# espDash.net
KiCad netlist of a schematic drawn in EAGLE
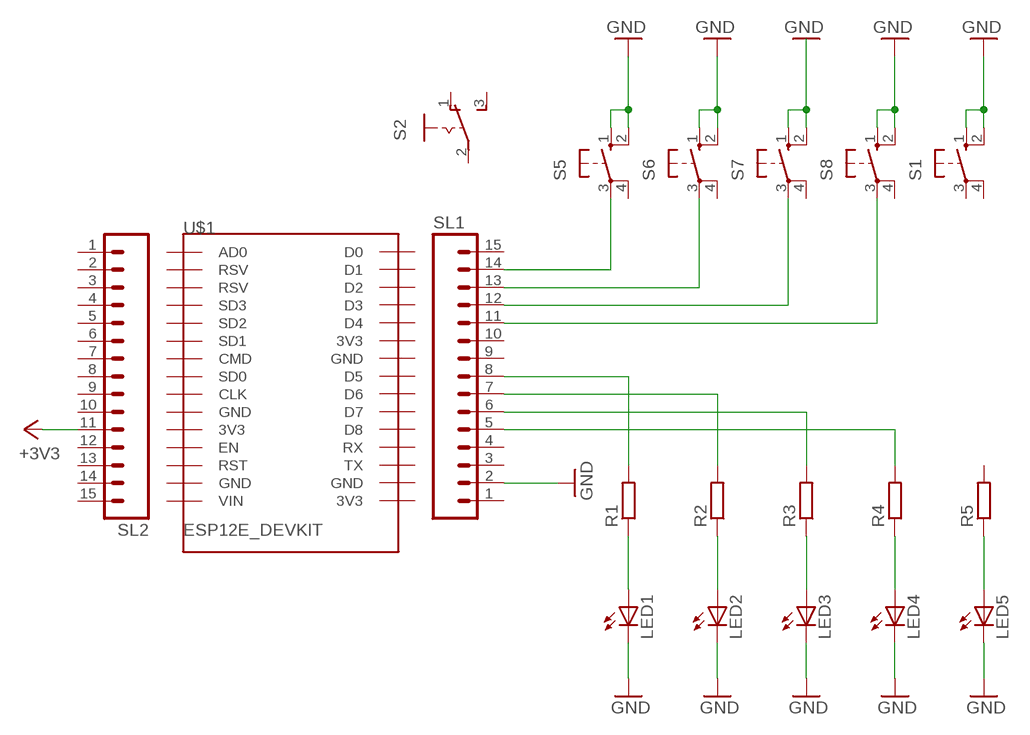
[diagram p0: schematic, sheet 1]

(export (version "E")
  (design (tool "Eeschema 10.0.6"))
  (components
    (comp (ref "LED1")
      (value "LED5MM")
      (footprint "eagle-import:LED5MM")
      (libsource (lib "eagle-import") (part "LED5MM"))
    )
    (comp (ref "LED2")
      (value "LED5MM")
      (footprint "eagle-import:LED5MM")
      (libsource (lib "eagle-import") (part "LED5MM"))
    )
    (comp (ref "LED3")
      (value "LED5MM")
      (footprint "eagle-import:LED5MM")
      (libsource (lib "eagle-import") (part "LED5MM"))
    )
    (comp (ref "LED4")
      (value "LED5MM")
      (footprint "eagle-import:LED5MM")
      (libsource (lib "eagle-import") (part "LED5MM"))
    )
    (comp (ref "LED5")
      (value "LED5MM")
      (footprint "eagle-import:LED5MM")
      (libsource (lib "eagle-import") (part "LED5MM"))
    )
    (comp (ref "R1")
      (value "R-EU_0207/10")
      (footprint "eagle-import:0207_10")
      (libsource (lib "eagle-import") (part "R-EU_0207/10"))
    )
    (comp (ref "R2")
      (value "R-EU_0207/10")
      (footprint "eagle-import:0207_10")
      (libsource (lib "eagle-import") (part "R-EU_0207/10"))
    )
    (comp (ref "R3")
      (value "R-EU_0207/10")
      (footprint "eagle-import:0207_10")
      (libsource (lib "eagle-import") (part "R-EU_0207/10"))
    )
    (comp (ref "R4")
      (value "R-EU_0207/10")
      (footprint "eagle-import:0207_10")
      (libsource (lib "eagle-import") (part "R-EU_0207/10"))
    )
    (comp (ref "R5")
      (value "R-EU_0207/10")
      (footprint "eagle-import:0207_10")
      (libsource (lib "eagle-import") (part "R-EU_0207/10"))
    )
    (comp (ref "S1")
      (value "40-XX")
      (footprint "eagle-import:B3F-40XX")
      (fields (field (name "MF") "OMRON COMPONENTS USA") (field (name "MPN") "B3F-4000"))
      (libsource (lib "eagle-import") (part "40-XX"))
    )
    (comp (ref "S2")
      (value "M251")
      (footprint "eagle-import:M251")
      (libsource (lib "eagle-import") (part "M251"))
    )
    (comp (ref "S5")
      (value "40-XX")
      (footprint "eagle-import:B3F-40XX")
      (fields (field (name "MF") "OMRON COMPONENTS USA") (field (name "MPN") "B3F-4000"))
      (libsource (lib "eagle-import") (part "40-XX"))
    )
    (comp (ref "S6")
      (value "40-XX")
      (footprint "eagle-import:B3F-40XX")
      (fields (field (name "MF") "OMRON COMPONENTS USA") (field (name "MPN") "B3F-4000"))
      (libsource (lib "eagle-import") (part "40-XX"))
    )
    (comp (ref "S7")
      (value "40-XX")
      (footprint "eagle-import:B3F-40XX")
      (fields (field (name "MF") "OMRON COMPONENTS USA") (field (name "MPN") "B3F-4000"))
      (libsource (lib "eagle-import") (part "40-XX"))
    )
    (comp (ref "S8")
      (value "40-XX")
      (footprint "eagle-import:B3F-40XX")
      (fields (field (name "MF") "OMRON COMPONENTS USA") (field (name "MPN") "B3F-4000"))
      (libsource (lib "eagle-import") (part "40-XX"))
    )
    (comp (ref "SL1")
      (value "M15")
      (footprint "eagle-import:15P")
      (libsource (lib "eagle-import") (part "M15"))
    )
    (comp (ref "SL2")
      (value "M15")
      (footprint "eagle-import:15P")
      (libsource (lib "eagle-import") (part "M15"))
    )
    (comp (ref "U$1")
      (value "ESP12E_DEVKIT")
      (footprint "eagle-import:ESP12E_DEVKIT")
      (libsource (lib "eagle-import") (part "ESP12E_DEVKIT"))
    )
  )
  (nets
    (net (code "1") (name "+3V3") (class "Default")
      (node (ref "SL2") (pin "11") (pinfunction "11_11") (pintype "passive"))
    )
    (net (code "2") (name "GND") (class "Default")
      (node (ref "LED1") (pin "K") (pinfunction "C_K") (pintype "passive"))
      (node (ref "LED2") (pin "K") (pinfunction "C_K") (pintype "passive"))
      (node (ref "LED3") (pin "K") (pinfunction "C_K") (pintype "passive"))
      (node (ref "LED4") (pin "K") (pinfunction "C_K") (pintype "passive"))
      (node (ref "LED5") (pin "K") (pinfunction "C_K") (pintype "passive"))
      (node (ref "S1") (pin "1") (pinfunction "S_1") (pintype "passive"))
      (node (ref "S1") (pin "2") (pinfunction "S1_2") (pintype "passive"))
      (node (ref "S5") (pin "1") (pinfunction "S_1") (pintype "passive"))
      (node (ref "S5") (pin "2") (pinfunction "S1_2") (pintype "passive"))
      (node (ref "S6") (pin "1") (pinfunction "S_1") (pintype "passive"))
      (node (ref "S6") (pin "2") (pinfunction "S1_2") (pintype "passive"))
      (node (ref "S8") (pin "1") (pinfunction "S_1") (pintype "passive"))
      (node (ref "S8") (pin "2") (pinfunction "S1_2") (pintype "passive"))
      (node (ref "SL1") (pin "2") (pinfunction "2_2") (pintype "passive"))
    )
    (net (code "3") (name "Net-(LED1-PadA)") (class "Default")
      (node (ref "LED1") (pin "A") (pinfunction "A_A") (pintype "passive"))
      (node (ref "R1") (pin "1") (pinfunction "1_1") (pintype "passive"))
    )
    (net (code "4") (name "Net-(LED2-PadA)") (class "Default")
      (node (ref "LED2") (pin "A") (pinfunction "A_A") (pintype "passive"))
      (node (ref "R2") (pin "1") (pinfunction "1_1") (pintype "passive"))
    )
    (net (code "5") (name "Net-(LED3-PadA)") (class "Default")
      (node (ref "LED3") (pin "A") (pinfunction "A_A") (pintype "passive"))
      (node (ref "R3") (pin "1") (pinfunction "1_1") (pintype "passive"))
    )
    (net (code "6") (name "Net-(LED4-PadA)") (class "Default")
      (node (ref "LED4") (pin "A") (pinfunction "A_A") (pintype "passive"))
      (node (ref "R4") (pin "1") (pinfunction "1_1") (pintype "passive"))
    )
    (net (code "7") (name "Net-(LED5-PadA)") (class "Default")
      (node (ref "LED5") (pin "A") (pinfunction "A_A") (pintype "passive"))
      (node (ref "R5") (pin "1") (pinfunction "1_1") (pintype "passive"))
    )
    (net (code "8") (name "Net-(R1-Pad2)") (class "Default")
      (node (ref "R1") (pin "2") (pinfunction "2_2") (pintype "passive"))
      (node (ref "SL1") (pin "8") (pinfunction "8_8") (pintype "passive"))
    )
    (net (code "9") (name "Net-(R2-Pad2)") (class "Default")
      (node (ref "R2") (pin "2") (pinfunction "2_2") (pintype "passive"))
      (node (ref "SL1") (pin "7") (pinfunction "7_7") (pintype "passive"))
    )
    (net (code "10") (name "Net-(R3-Pad2)") (class "Default")
      (node (ref "R3") (pin "2") (pinfunction "2_2") (pintype "passive"))
      (node (ref "SL1") (pin "6") (pinfunction "6_6") (pintype "passive"))
    )
    (net (code "11") (name "Net-(R4-Pad2)") (class "Default")
      (node (ref "R4") (pin "2") (pinfunction "2_2") (pintype "passive"))
      (node (ref "SL1") (pin "5") (pinfunction "5_5") (pintype "passive"))
    )
    (net (code "12") (name "Net-(S5-P)") (class "Default")
      (node (ref "S5") (pin "3") (pinfunction "P_3") (pintype "passive"))
      (node (ref "SL1") (pin "14") (pinfunction "14_14") (pintype "passive"))
    )
    (net (code "13") (name "Net-(S6-P)") (class "Default")
      (node (ref "S6") (pin "3") (pinfunction "P_3") (pintype "passive"))
      (node (ref "SL1") (pin "13") (pinfunction "13_13") (pintype "passive"))
    )
    (net (code "14") (name "Net-(S7-P)") (class "Default")
      (node (ref "S7") (pin "3") (pinfunction "P_3") (pintype "passive"))
      (node (ref "SL1") (pin "12") (pinfunction "12_12") (pintype "passive"))
    )
    (net (code "15") (name "Net-(S7-S)") (class "Default")
      (node (ref "S7") (pin "1") (pinfunction "S_1") (pintype "passive"))
      (node (ref "S7") (pin "2") (pinfunction "S1_2") (pintype "passive"))
    )
    (net (code "16") (name "Net-(S8-P)") (class "Default")
      (node (ref "S8") (pin "3") (pinfunction "P_3") (pintype "passive"))
      (node (ref "SL1") (pin "11") (pinfunction "11_11") (pintype "passive"))
    )
    (net (code "17") (name "unconnected-(R5-Pad2)") (class "Default")
      (node (ref "R5") (pin "2") (pinfunction "2_2") (pintype "passive"))
    )
    (net (code "18") (name "unconnected-(S1-P-Pad3)") (class "Default")
      (node (ref "S1") (pin "3") (pinfunction "P_3") (pintype "passive"))
    )
    (net (code "19") (name "unconnected-(S1-P1-Pad4)") (class "Default")
      (node (ref "S1") (pin "4") (pinfunction "P1_4") (pintype "passive"))
    )
    (net (code "20") (name "unconnected-(S2-O-Pad1)") (class "Default")
      (node (ref "S2") (pin "1") (pinfunction "O_1") (pintype "passive"))
    )
    (net (code "21") (name "unconnected-(S2-P-Pad2)") (class "Default")
      (node (ref "S2") (pin "2") (pinfunction "P_2") (pintype "passive"))
    )
    (net (code "22") (name "unconnected-(S2-S-Pad3)") (class "Default")
      (node (ref "S2") (pin "3") (pinfunction "S_3") (pintype "passive"))
    )
    (net (code "23") (name "unconnected-(S5-P1-Pad4)") (class "Default")
      (node (ref "S5") (pin "4") (pinfunction "P1_4") (pintype "passive"))
    )
    (net (code "24") (name "unconnected-(S6-P1-Pad4)") (class "Default")
      (node (ref "S6") (pin "4") (pinfunction "P1_4") (pintype "passive"))
    )
    (net (code "25") (name "unconnected-(S7-P1-Pad4)") (class "Default")
      (node (ref "S7") (pin "4") (pinfunction "P1_4") (pintype "passive"))
    )
    (net (code "26") (name "unconnected-(S8-P1-Pad4)") (class "Default")
      (node (ref "S8") (pin "4") (pinfunction "P1_4") (pintype "passive"))
    )
    (net (code "27") (name "unconnected-(SL1-Pad1)") (class "Default")
      (node (ref "SL1") (pin "1") (pinfunction "1_1") (pintype "passive"))
    )
    (net (code "28") (name "unconnected-(SL1-Pad3)") (class "Default")
      (node (ref "SL1") (pin "3") (pinfunction "3_3") (pintype "passive"))
    )
    (net (code "29") (name "unconnected-(SL1-Pad4)") (class "Default")
      (node (ref "SL1") (pin "4") (pinfunction "4_4") (pintype "passive"))
    )
    (net (code "30") (name "unconnected-(SL1-Pad9)") (class "Default")
      (node (ref "SL1") (pin "9") (pinfunction "9_9") (pintype "passive"))
    )
    (net (code "31") (name "unconnected-(SL1-Pad10)") (class "Default")
      (node (ref "SL1") (pin "10") (pinfunction "10_10") (pintype "passive"))
    )
    (net (code "32") (name "unconnected-(SL1-Pad15)") (class "Default")
      (node (ref "SL1") (pin "15") (pinfunction "15_15") (pintype "passive"))
    )
    (net (code "33") (name "unconnected-(SL2-Pad1)") (class "Default")
      (node (ref "SL2") (pin "1") (pinfunction "1_1") (pintype "passive"))
    )
    (net (code "34") (name "unconnected-(SL2-Pad2)") (class "Default")
      (node (ref "SL2") (pin "2") (pinfunction "2_2") (pintype "passive"))
    )
    (net (code "35") (name "unconnected-(SL2-Pad3)") (class "Default")
      (node (ref "SL2") (pin "3") (pinfunction "3_3") (pintype "passive"))
    )
    (net (code "36") (name "unconnected-(SL2-Pad4)") (class "Default")
      (node (ref "SL2") (pin "4") (pinfunction "4_4") (pintype "passive"))
    )
    (net (code "37") (name "unconnected-(SL2-Pad5)") (class "Default")
      (node (ref "SL2") (pin "5") (pinfunction "5_5") (pintype "passive"))
    )
    (net (code "38") (name "unconnected-(SL2-Pad6)") (class "Default")
      (node (ref "SL2") (pin "6") (pinfunction "6_6") (pintype "passive"))
    )
    (net (code "39") (name "unconnected-(SL2-Pad7)") (class "Default")
      (node (ref "SL2") (pin "7") (pinfunction "7_7") (pintype "passive"))
    )
    (net (code "40") (name "unconnected-(SL2-Pad8)") (class "Default")
      (node (ref "SL2") (pin "8") (pinfunction "8_8") (pintype "passive"))
    )
    (net (code "41") (name "unconnected-(SL2-Pad9)") (class "Default")
      (node (ref "SL2") (pin "9") (pinfunction "9_9") (pintype "passive"))
    )
    (net (code "42") (name "unconnected-(SL2-Pad10)") (class "Default")
      (node (ref "SL2") (pin "10") (pinfunction "10_10") (pintype "passive"))
    )
    (net (code "43") (name "unconnected-(SL2-Pad12)") (class "Default")
      (node (ref "SL2") (pin "12") (pinfunction "12_12") (pintype "passive"))
    )
    (net (code "44") (name "unconnected-(SL2-Pad13)") (class "Default")
      (node (ref "SL2") (pin "13") (pinfunction "13_13") (pintype "passive"))
    )
    (net (code "45") (name "unconnected-(SL2-Pad14)") (class "Default")
      (node (ref "SL2") (pin "14") (pinfunction "14_14") (pintype "passive"))
    )
    (net (code "46") (name "unconnected-(SL2-Pad15)") (class "Default")
      (node (ref "SL2") (pin "15") (pinfunction "15_15") (pintype "passive"))
    )
    (net (code "47") (name "unconnected-(U$1-3V3-Pad3V3@0)") (class "Default")
      (node (ref "U$1") (pin "3V3@0") (pinfunction "3V3_3V3@0") (pintype "bidirectional"))
    )
    (net (code "48") (name "unconnected-(U$1-3V3-Pad3V3@1)") (class "Default")
      (node (ref "U$1") (pin "3V3@1") (pinfunction "3V3_3V3@1") (pintype "bidirectional"))
    )
    (net (code "49") (name "unconnected-(U$1-3V3-Pad3V3@2)") (class "Default")
      (node (ref "U$1") (pin "3V3@2") (pinfunction "3V3_3V3@2") (pintype "bidirectional"))
    )
    (net (code "50") (name "unconnected-(U$1-GND-PadGND@0)") (class "Default")
      (node (ref "U$1") (pin "GND@0") (pinfunction "GND_GND@0") (pintype "bidirectional"))
    )
    (net (code "51") (name "unconnected-(U$1-GND-PadGND@1)") (class "Default")
      (node (ref "U$1") (pin "GND@1") (pinfunction "GND_GND@1") (pintype "bidirectional"))
    )
    (net (code "52") (name "unconnected-(U$1-GND-PadGND@2)") (class "Default")
      (node (ref "U$1") (pin "GND@2") (pinfunction "GND_GND@2") (pintype "bidirectional"))
    )
    (net (code "53") (name "unconnected-(U$1-GND-PadGND@3)") (class "Default")
      (node (ref "U$1") (pin "GND@3") (pinfunction "GND_GND@3") (pintype "bidirectional"))
    )
    (net (code "54") (name "unconnected-(U$1-PadAD0)") (class "Default")
      (node (ref "U$1") (pin "AD0") (pinfunction "AD0_AD0") (pintype "bidirectional"))
    )
    (net (code "55") (name "unconnected-(U$1-PadCLK)") (class "Default")
      (node (ref "U$1") (pin "CLK") (pinfunction "CLK_CLK") (pintype "bidirectional"))
    )
    (net (code "56") (name "unconnected-(U$1-PadCMD)") (class "Default")
      (node (ref "U$1") (pin "CMD") (pinfunction "CMD_CMD") (pintype "bidirectional"))
    )
    (net (code "57") (name "unconnected-(U$1-PadD0)") (class "Default")
      (node (ref "U$1") (pin "D0") (pinfunction "D0_D0") (pintype "bidirectional"))
    )
    (net (code "58") (name "unconnected-(U$1-PadD1)") (class "Default")
      (node (ref "U$1") (pin "D1") (pinfunction "D1_D1") (pintype "bidirectional"))
    )
    (net (code "59") (name "unconnected-(U$1-PadD2)") (class "Default")
      (node (ref "U$1") (pin "D2") (pinfunction "D2_D2") (pintype "bidirectional"))
    )
    (net (code "60") (name "unconnected-(U$1-PadD3)") (class "Default")
      (node (ref "U$1") (pin "D3") (pinfunction "D3_D3") (pintype "bidirectional"))
    )
    (net (code "61") (name "unconnected-(U$1-PadD4)") (class "Default")
      (node (ref "U$1") (pin "D4") (pinfunction "D4_D4") (pintype "bidirectional"))
    )
    (net (code "62") (name "unconnected-(U$1-PadD5)") (class "Default")
      (node (ref "U$1") (pin "D5") (pinfunction "D5_D5") (pintype "bidirectional"))
    )
    (net (code "63") (name "unconnected-(U$1-PadD6)") (class "Default")
      (node (ref "U$1") (pin "D6") (pinfunction "D6_D6") (pintype "bidirectional"))
    )
    (net (code "64") (name "unconnected-(U$1-PadD7)") (class "Default")
      (node (ref "U$1") (pin "D7") (pinfunction "D7_D7") (pintype "bidirectional"))
    )
    (net (code "65") (name "unconnected-(U$1-PadD8)") (class "Default")
      (node (ref "U$1") (pin "D8") (pinfunction "D8_D8") (pintype "bidirectional"))
    )
    (net (code "66") (name "unconnected-(U$1-PadEN)") (class "Default")
      (node (ref "U$1") (pin "EN") (pinfunction "EN_EN") (pintype "bidirectional"))
    )
    (net (code "67") (name "unconnected-(U$1-PadRST)") (class "Default")
      (node (ref "U$1") (pin "RST") (pinfunction "RST_RST") (pintype "bidirectional"))
    )
    (net (code "68") (name "unconnected-(U$1-PadRX)") (class "Default")
      (node (ref "U$1") (pin "RX") (pinfunction "RX_RX") (pintype "bidirectional"))
    )
    (net (code "69") (name "unconnected-(U$1-PadSD0)") (class "Default")
      (node (ref "U$1") (pin "SD0") (pinfunction "SD0_SD0") (pintype "bidirectional"))
    )
    (net (code "70") (name "unconnected-(U$1-PadSD1)") (class "Default")
      (node (ref "U$1") (pin "SD1") (pinfunction "SD1_SD1") (pintype "bidirectional"))
    )
    (net (code "71") (name "unconnected-(U$1-PadSD2)") (class "Default")
      (node (ref "U$1") (pin "SD2") (pinfunction "SD2_SD2") (pintype "bidirectional"))
    )
    (net (code "72") (name "unconnected-(U$1-PadSD3)") (class "Default")
      (node (ref "U$1") (pin "SD3") (pinfunction "SD3_SD3") (pintype "bidirectional"))
    )
    (net (code "73") (name "unconnected-(U$1-PadTX)") (class "Default")
      (node (ref "U$1") (pin "TX") (pinfunction "TX_TX") (pintype "bidirectional"))
    )
    (net (code "74") (name "unconnected-(U$1-PadVIN)") (class "Default")
      (node (ref "U$1") (pin "VIN") (pinfunction "VIN_VIN") (pintype "bidirectional"))
    )
    (net (code "75") (name "unconnected-(U$1-RSV-PadRSV@0)") (class "Default")
      (node (ref "U$1") (pin "RSV@0") (pinfunction "RSV_RSV@0") (pintype "bidirectional"))
    )
    (net (code "76") (name "unconnected-(U$1-RSV-PadRSV@1)") (class "Default")
      (node (ref "U$1") (pin "RSV@1") (pinfunction "RSV_RSV@1") (pintype "bidirectional"))
    )
  )
)
